# sendai.net
KiCad netlist of a schematic drawn in EAGLE
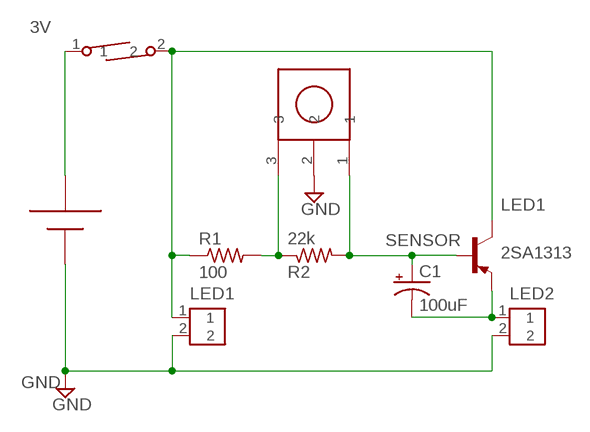
[diagram p0: schematic, sheet 1]

(export (version "E")
  (design (tool "Eeschema 10.0.6"))
  (components
    (comp (ref "C1")
      (value "100uF")
      (footprint "eagle-import:TT2D6")
      (libsource (lib "eagle-import") (part "CPOL-USTT2D6"))
    )
    (comp (ref "R1")
      (value "100")
      (footprint "eagle-import:R0603")
      (libsource (lib "eagle-import") (part "R-US_R0603"))
    )
    (comp (ref "R2")
      (value "22k")
      (footprint "eagle-import:R0603")
      (libsource (lib "eagle-import") (part "R-US_R0603"))
    )
    (comp (ref "T1")
      (value "2SA1313")
      (footprint "eagle-import:SOT23-BEC")
      (libsource (lib "eagle-import") (part "-PNP-SOT23-BEC"))
    )
    (comp (ref "U$1")
      (value "CR2032_VCR2032_V")
      (footprint "eagle-import:CR2032_V")
      (libsource (lib "eagle-import") (part "CR2032_VCR2032_V"))
    )
    (comp (ref "U$2")
      (value "CONNECTER_CON2")
      (footprint "eagle-import:CONNECTER_CON2")
      (libsource (lib "eagle-import") (part "CONNECTER_CON2"))
    )
    (comp (ref "U$3")
      (value "CONNECTER_CON2")
      (footprint "eagle-import:CONNECTER_CON2")
      (libsource (lib "eagle-import") (part "CONNECTER_CON2"))
    )
    (comp (ref "U$4")
      (value "LEAD_SWITCH_LEAD_SWITCH")
      (footprint "eagle-import:LEAD_SWITCH_LEAD_SWITCH")
      (libsource (lib "eagle-import") (part "LEAD_SWITCH_LEAD_SWITCH"))
    )
    (comp (ref "U$5")
      (value "OSRB38C9AA")
      (footprint "eagle-import:OSRB38C9AA")
      (libsource (lib "eagle-import") (part "OSRB38C9AA"))
    )
  )
  (nets
    (net (code "1") (name "/3V") (class "Default")
      (node (ref "U$1") (pin "3") (pinfunction "+_3") (pintype "bidirectional"))
      (node (ref "U$4") (pin "1") (pinfunction "1_1") (pintype "bidirectional"))
    )
    (net (code "2") (name "/LED1") (class "Default")
      (node (ref "R1") (pin "1") (pinfunction "1_1") (pintype "passive"))
      (node (ref "T1") (pin "C") (pinfunction "C_C") (pintype "passive"))
      (node (ref "U$2") (pin "1") (pinfunction "1_1") (pintype "bidirectional"))
      (node (ref "U$4") (pin "2") (pinfunction "2_2") (pintype "bidirectional"))
    )
    (net (code "3") (name "/LED2") (class "Default")
      (node (ref "C1") (pin "-") (pinfunction "-_-") (pintype "passive"))
      (node (ref "T1") (pin "E") (pinfunction "E_E") (pintype "passive"))
      (node (ref "U$3") (pin "1") (pinfunction "1_1") (pintype "bidirectional"))
    )
    (net (code "4") (name "/SENSOR") (class "Default")
      (node (ref "C1") (pin "+") (pinfunction "+_+") (pintype "passive"))
      (node (ref "R2") (pin "2") (pinfunction "2_2") (pintype "passive"))
      (node (ref "T1") (pin "B") (pinfunction "B_B") (pintype "passive"))
      (node (ref "U$5") (pin "1") (pinfunction "1_1") (pintype "bidirectional"))
    )
    (net (code "5") (name "GND") (class "Default")
      (node (ref "U$1") (pin "2") (pinfunction "-_2") (pintype "bidirectional"))
      (node (ref "U$2") (pin "2") (pinfunction "2_2") (pintype "bidirectional"))
      (node (ref "U$3") (pin "2") (pinfunction "2_2") (pintype "bidirectional"))
      (node (ref "U$5") (pin "2") (pinfunction "2_2") (pintype "bidirectional"))
    )
    (net (code "6") (name "Net-(R1-Pad2)") (class "Default")
      (node (ref "R1") (pin "2") (pinfunction "2_2") (pintype "passive"))
      (node (ref "R2") (pin "1") (pinfunction "1_1") (pintype "passive"))
      (node (ref "U$5") (pin "3") (pinfunction "3_3") (pintype "bidirectional"))
    )
  )
)
